# Schematic_Radio_EasyEDA.net
KiCad netlist of a schematic drawn in EasyEDA
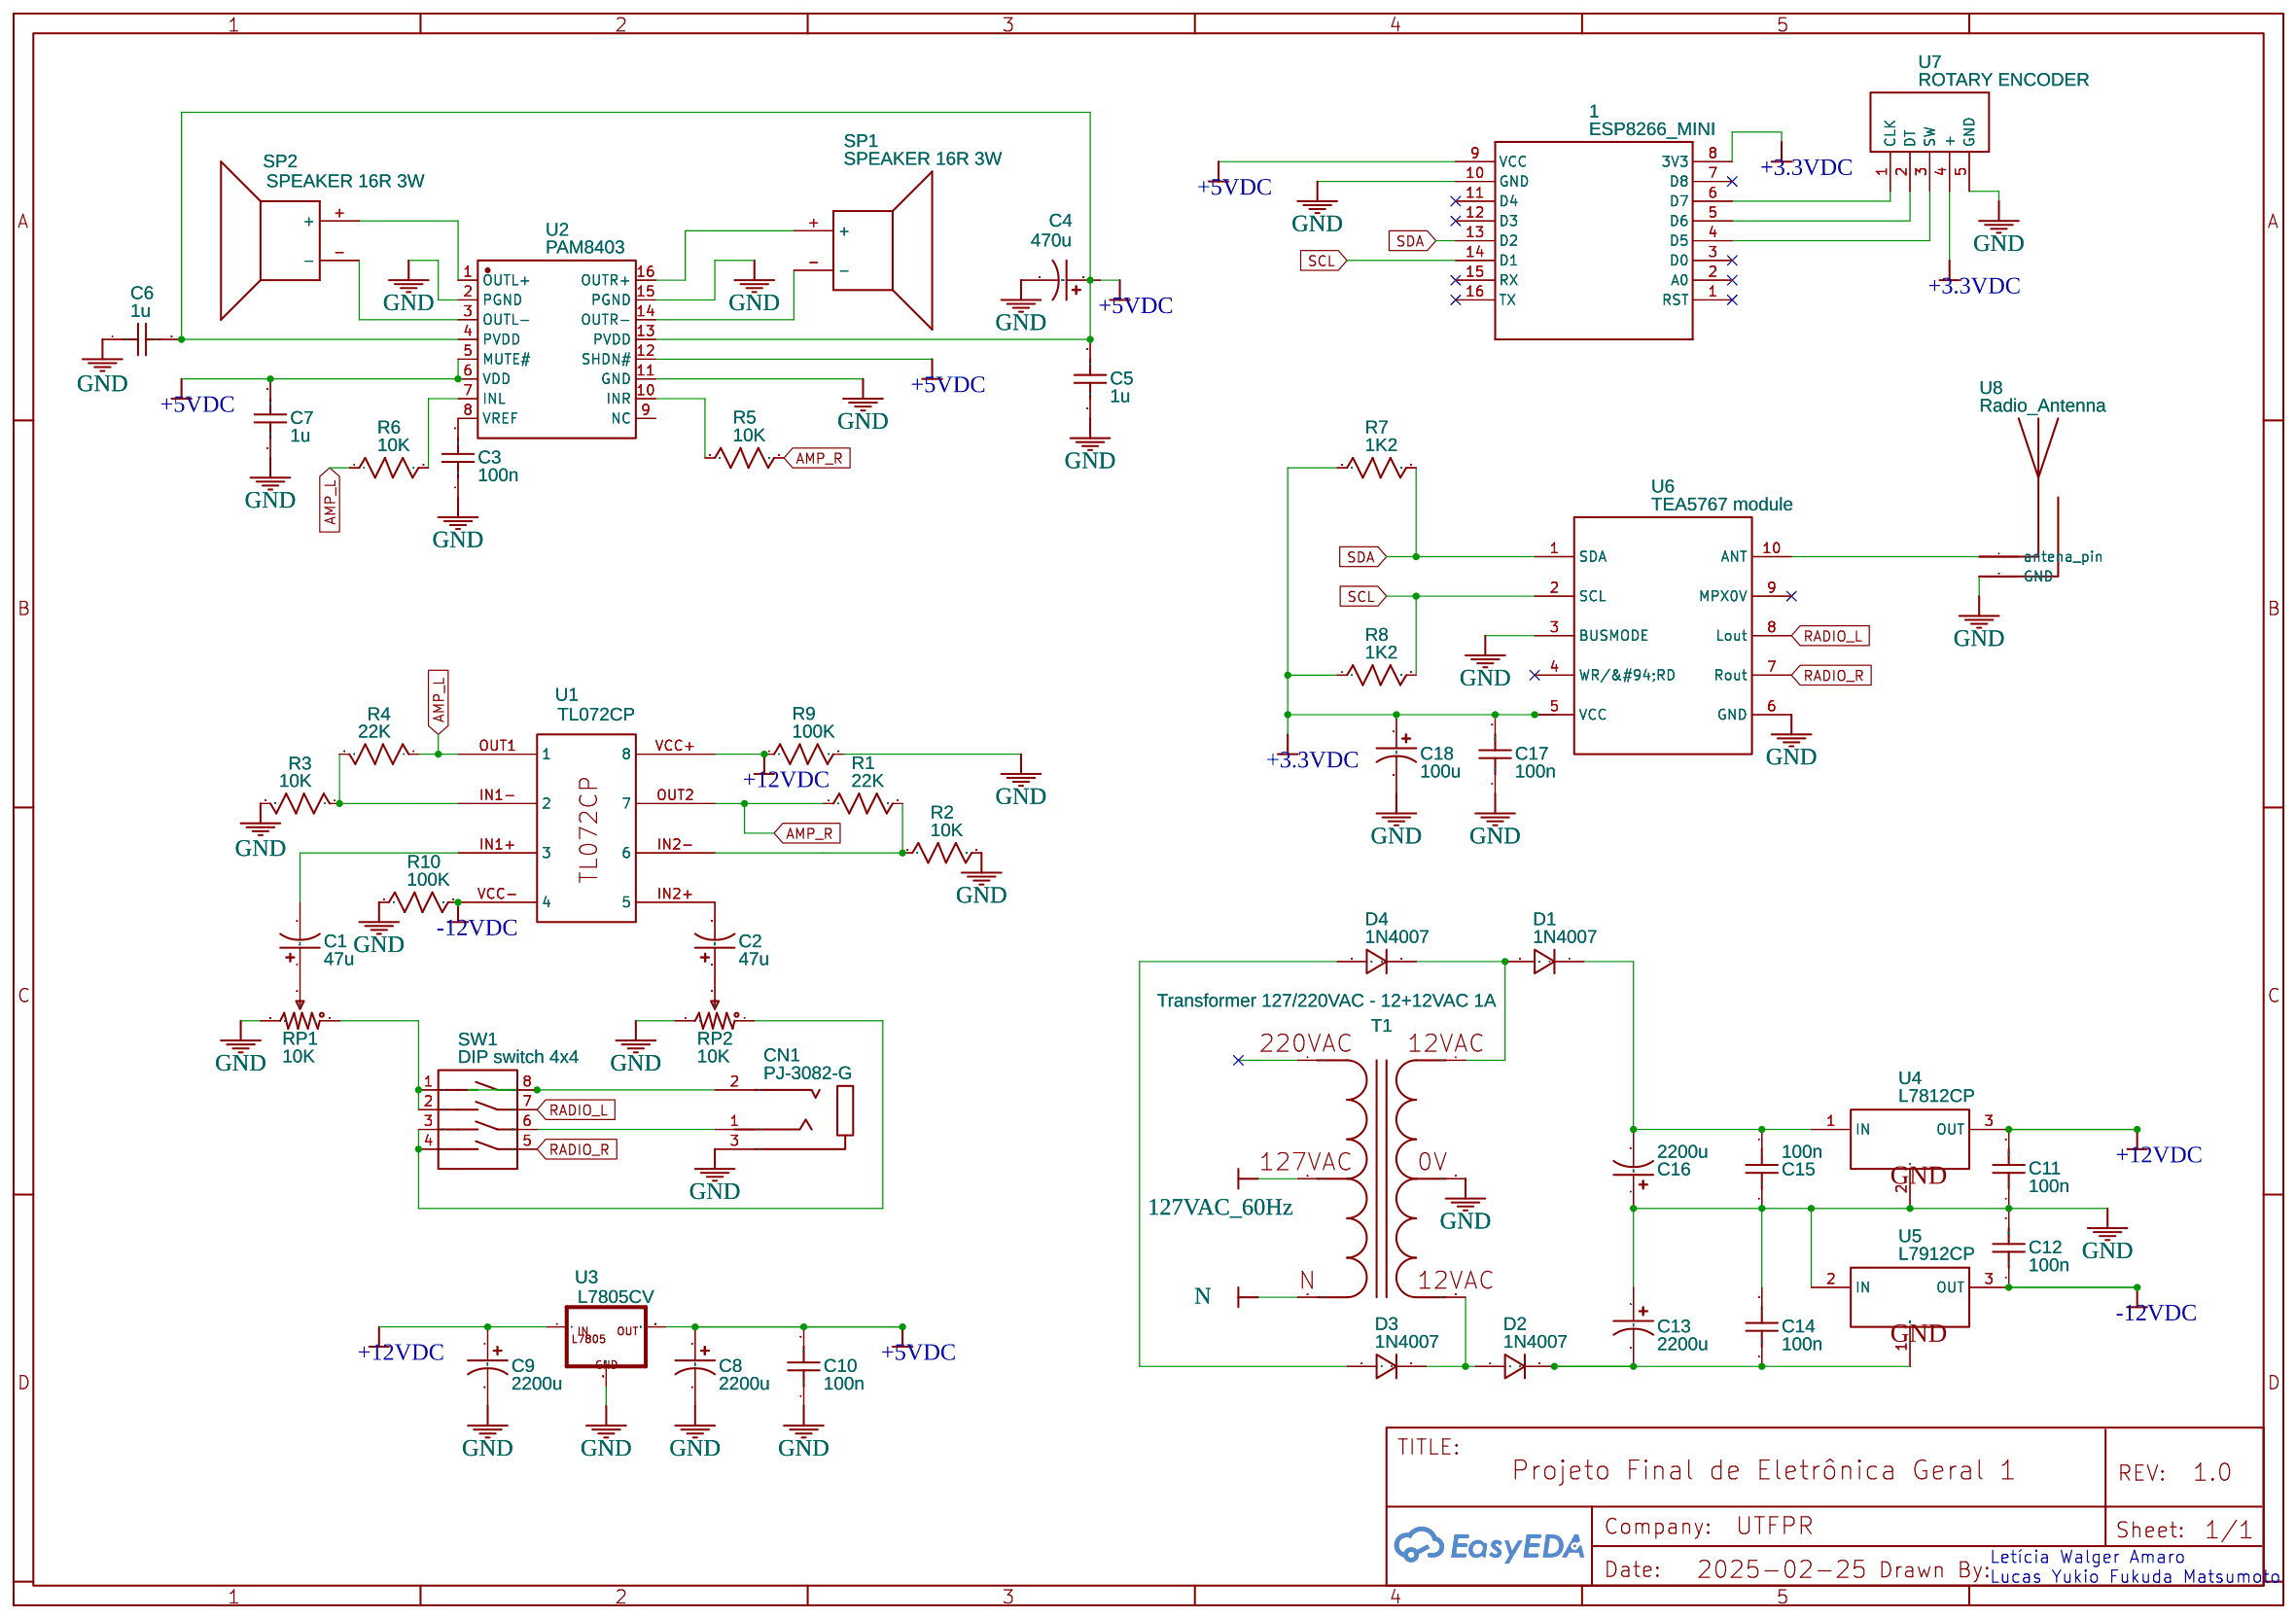
[diagram p0: schematic sheet]

(export (version "E")
  (design (tool "Eeschema 10.0.6"))
  (components
    (comp (ref "1") (value "ESP8266_MINI") (libsource (lib "") (part "ESP8266MINI COPY")))
    (comp (ref "C1") (value "47u") (libsource (lib "") (part "C_Tan_SMD_A_US_5")))
    (comp (ref "C2") (value "47u") (libsource (lib "") (part "C_Tan_SMD_A_US_2")))
    (comp (ref "C3") (value "100n") (libsource (lib "") (part "C_0603_US")))
    (comp (ref "C4") (value "470u") (libsource (lib "") (part "C_Tan_SMD_A_US_3")))
    (comp (ref "C5") (value "1u") (libsource (lib "") (part "C_0603_US")))
    (comp (ref "C6") (value "1u") (libsource (lib "") (part "C_0603_US_1")))
    (comp (ref "C7") (value "1u") (libsource (lib "") (part "C_0603_US")))
    (comp (ref "C8") (value "2200u") (libsource (lib "") (part "C_Tan_SMD_A_US_1")))
    (comp (ref "C9") (value "2200u") (libsource (lib "") (part "C_Tan_SMD_A_US_4")))
    (comp (ref "C10") (value "100n") (libsource (lib "") (part "C_0603_US")))
    (comp (ref "C11") (value "100n") (libsource (lib "") (part "C_0603_US")))
    (comp (ref "C12") (value "100n") (libsource (lib "") (part "C_0603_US")))
    (comp (ref "C13") (value "2200u") (libsource (lib "") (part "C_Tan_SMD_A_US_1")))
    (comp (ref "C14") (value "100n") (libsource (lib "") (part "C_0603_US")))
    (comp (ref "C15") (value "100n") (libsource (lib "") (part "C_0603_US_2")))
    (comp (ref "C16") (value "2200u") (libsource (lib "") (part "C_Tan_SMD_A_US")))
    (comp (ref "C17") (value "100n") (libsource (lib "") (part "C_0603_US")))
    (comp (ref "C18") (value "100u") (libsource (lib "") (part "C_Tan_SMD_A_US_6")))
    (comp (ref "CN1")
      (value "PJ-3082-G")
      (fields
        (field (name "Manufacturer Part") "PJ-3733")
        (field (name "Manufacturer") "XKB Connection(中国星坤)")
      )
      (libsource (lib "") (part "PJ-3733"))
    )
    (comp (ref "D1")
      (value "1N4007")
      (fields (field (name "Manufacturer Part") "1N4007W") (field (name "Manufacturer") "BLUE ROCKET"))
      (libsource (lib "") (part "1N4007W"))
    )
    (comp (ref "D2")
      (value "1N4007")
      (fields (field (name "Manufacturer Part") "1N4007W") (field (name "Manufacturer") "BLUE ROCKET"))
      (libsource (lib "") (part "1N4007W"))
    )
    (comp (ref "D3")
      (value "1N4007")
      (fields (field (name "Manufacturer Part") "1N4007W") (field (name "Manufacturer") "BLUE ROCKET"))
      (libsource (lib "") (part "1N4007W"))
    )
    (comp (ref "D4")
      (value "1N4007")
      (fields (field (name "Manufacturer Part") "1N4007W") (field (name "Manufacturer") "BLUE ROCKET"))
      (libsource (lib "") (part "1N4007W"))
    )
    (comp (ref "R1") (value "22K") (libsource (lib "") (part "R_0603_US_1")))
    (comp (ref "R2") (value "10K") (libsource (lib "") (part "R_0603_US_1")))
    (comp (ref "R3") (value "10K") (libsource (lib "") (part "R_0603_US")))
    (comp (ref "R4") (value "22K") (libsource (lib "") (part "R_0603_US")))
    (comp (ref "R5") (value "10K") (libsource (lib "") (part "R_0603_US_1")))
    (comp (ref "R6") (value "10K") (libsource (lib "") (part "R_0603_US_1")))
    (comp (ref "R7") (value "1K2") (libsource (lib "") (part "R_0603_US_1")))
    (comp (ref "R8") (value "1K2") (libsource (lib "") (part "R_0603_US_1")))
    (comp (ref "R9") (value "100K") (libsource (lib "") (part "R_0603_US_1")))
    (comp (ref "R10") (value "100K") (libsource (lib "") (part "R_0603_US_1")))
    (comp (ref "RP1") (value "10K") (libsource (lib "") (part "R_3386P_US")))
    (comp (ref "RP2") (value "10K") (libsource (lib "") (part "R_3386P_US")))
    (comp (ref "SP1") (value "SPEAKER 16R 3W") (libsource (lib "") (part "SPEAKER_1")))
    (comp (ref "SP2") (value "SPEAKER 16R 3W") (libsource (lib "") (part "SPEAKER")))
    (comp (ref "SW1")
      (value "DIP switch 4x4")
      (fields (field (name "Manufacturer Part") "拨码开关EI-04") (field (name "Manufacturer") "圜达"))
      (libsource (lib "") (part "DIP switchEI-04"))
    )
    (comp (ref "T1")
      (value "Transformer 127/220VAC - 12+12VAC 1A")
      (fields (field (name "Manufacturer Part") "TTG-6C33CPP") (field (name "Manufacturer") "Toroidy"))
      (libsource (lib "") (part "Transformer"))
    )
    (comp (ref "U1")
      (value "TL072CP")
      (fields (field (name "Manufacturer") "TI(德州仪器)"))
      (libsource (lib "") (part "TL072CP"))
    )
    (comp (ref "U2")
      (value "PAM8403")
      (fields (field (name "Manufacturer") "Slkor(萨科微)"))
      (libsource (lib "") (part "PAM8403"))
    )
    (comp (ref "U3") (value "L7805CV") (libsource (lib "") (part "-L7805")))
    (comp (ref "U4") (value "L7812CP") (libsource (lib "") (part "L7812CP")))
    (comp (ref "U5") (value "L7912CP") (libsource (lib "") (part "L7912CP")))
    (comp (ref "U6")
      (value "TEA5767 module")
      (fields (field (name "Manufacturer Part") "TEA5767"))
      (libsource (lib "") (part "TEA5767 module"))
    )
    (comp (ref "U7") (value "ROTARY ENCODER") (libsource (lib "") (part "ROTARY ENCODER (BREAKOUT)")))
    (comp (ref "U8") (value "Radio_Antenna") (libsource (lib "") (part "Radio_Antenna")))
  )
  (nets
    (net (code "1") (name "+3.3VDC") (class "Default")
      (node (ref "1") (pin "8") (pinfunction "3V3_8") (pintype "bidirectional"))
      (node (ref "C17") (pin "2") (pinfunction "2_2") (pintype "unspecified"))
      (node (ref "C18") (pin "1") (pinfunction "1_1") (pintype "unspecified"))
      (node (ref "R7") (pin "1") (pinfunction "1_1") (pintype "unspecified"))
      (node (ref "R8") (pin "1") (pinfunction "1_1") (pintype "unspecified"))
      (node (ref "U6") (pin "5") (pinfunction "VCC_5") (pintype "unspecified"))
      (node (ref "U7") (pin "4") (pinfunction "+_4") (pintype "unspecified"))
    )
    (net (code "2") (name "+5VDC") (class "Default")
      (node (ref "1") (pin "9") (pinfunction "VCC_9") (pintype "bidirectional"))
      (node (ref "C10") (pin "2") (pinfunction "2_2") (pintype "unspecified"))
      (node (ref "C4") (pin "1") (pinfunction "1_1") (pintype "unspecified"))
      (node (ref "C7") (pin "2") (pinfunction "2_2") (pintype "unspecified"))
      (node (ref "C8") (pin "1") (pinfunction "1_1") (pintype "unspecified"))
      (node (ref "U2") (pin "12") (pinfunction "SHDN#_12") (pintype "unspecified"))
      (node (ref "U2") (pin "5") (pinfunction "MUTE#_5") (pintype "unspecified"))
      (node (ref "U2") (pin "6") (pinfunction "VDD_6") (pintype "unspecified"))
      (node (ref "U3") (pin "OUT") (pinfunction "OUT_OUT") (pintype "unspecified"))
    )
    (net (code "3") (name "+12VDC") (class "Default")
      (node (ref "C11") (pin "2") (pinfunction "2_2") (pintype "unspecified"))
      (node (ref "C9") (pin "1") (pinfunction "1_1") (pintype "unspecified"))
      (node (ref "R9") (pin "1") (pinfunction "1_1") (pintype "unspecified"))
      (node (ref "U1") (pin "VCC+") (pinfunction "8_VCC+") (pintype "unspecified"))
      (node (ref "U3") (pin "IN") (pinfunction "IN_IN") (pintype "input"))
      (node (ref "U4") (pin "3") (pinfunction "OUT_3") (pintype "passive"))
    )
    (net (code "4") (name "-12VDC") (class "Default")
      (node (ref "C12") (pin "1") (pinfunction "1_1") (pintype "unspecified"))
      (node (ref "R10") (pin "2") (pinfunction "2_2") (pintype "unspecified"))
      (node (ref "U1") (pin "VCC-") (pinfunction "4_VCC-") (pintype "unspecified"))
      (node (ref "U5") (pin "3") (pinfunction "OUT_3") (pintype "passive"))
    )
    (net (code "5") (name "127VAC_60Hz") (class "Default")
      (node (ref "T1") (pin "2") (pinfunction "2_2") (pintype "unspecified"))
    )
    (net (code "6") (name "AMP_L") (class "Default")
      (node (ref "R4") (pin "1") (pinfunction "1_1") (pintype "unspecified"))
      (node (ref "R6") (pin "1") (pinfunction "1_1") (pintype "unspecified"))
      (node (ref "U1") (pin "OUT1") (pinfunction "1_OUT1") (pintype "unspecified"))
    )
    (net (code "7") (name "AMP_R") (class "Default")
      (node (ref "R1") (pin "1") (pinfunction "1_1") (pintype "unspecified"))
      (node (ref "R5") (pin "2") (pinfunction "2_2") (pintype "unspecified"))
      (node (ref "U1") (pin "OUT2") (pinfunction "7_OUT2") (pintype "unspecified"))
    )
    (net (code "8") (name "GND") (class "Default")
      (node (ref "1") (pin "10") (pinfunction "GND_10") (pintype "bidirectional"))
      (node (ref "C10") (pin "1") (pinfunction "1_1") (pintype "unspecified"))
      (node (ref "C11") (pin "1") (pinfunction "1_1") (pintype "unspecified"))
      (node (ref "C12") (pin "2") (pinfunction "2_2") (pintype "unspecified"))
      (node (ref "C13") (pin "1") (pinfunction "1_1") (pintype "unspecified"))
      (node (ref "C14") (pin "2") (pinfunction "2_2") (pintype "unspecified"))
      (node (ref "C15") (pin "2") (pinfunction "2_2") (pintype "unspecified"))
      (node (ref "C16") (pin "1") (pinfunction "1_1") (pintype "unspecified"))
      (node (ref "C17") (pin "1") (pinfunction "1_1") (pintype "unspecified"))
      (node (ref "C18") (pin "2") (pinfunction "2_2") (pintype "unspecified"))
      (node (ref "C3") (pin "1") (pinfunction "1_1") (pintype "unspecified"))
      (node (ref "C4") (pin "2") (pinfunction "2_2") (pintype "unspecified"))
      (node (ref "C5") (pin "1") (pinfunction "1_1") (pintype "unspecified"))
      (node (ref "C6") (pin "1") (pinfunction "1_1") (pintype "unspecified"))
      (node (ref "C7") (pin "1") (pinfunction "1_1") (pintype "unspecified"))
      (node (ref "C8") (pin "2") (pinfunction "2_2") (pintype "unspecified"))
      (node (ref "C9") (pin "2") (pinfunction "2_2") (pintype "unspecified"))
      (node (ref "CN1") (pin "3") (pinfunction "3_3") (pintype "unspecified"))
      (node (ref "R10") (pin "1") (pinfunction "1_1") (pintype "unspecified"))
      (node (ref "R2") (pin "2") (pinfunction "2_2") (pintype "unspecified"))
      (node (ref "R3") (pin "2") (pinfunction "2_2") (pintype "unspecified"))
      (node (ref "R9") (pin "2") (pinfunction "2_2") (pintype "unspecified"))
      (node (ref "RP1") (pin "3") (pinfunction "3_3") (pintype "unspecified"))
      (node (ref "RP2") (pin "3") (pinfunction "3_3") (pintype "unspecified"))
      (node (ref "T1") (pin "5") (pinfunction "5_5") (pintype "unspecified"))
      (node (ref "U2") (pin "11") (pinfunction "GND_11") (pintype "unspecified"))
      (node (ref "U2") (pin "15") (pinfunction "PGND_15") (pintype "unspecified"))
      (node (ref "U2") (pin "2") (pinfunction "PGND_2") (pintype "unspecified"))
      (node (ref "U3") (pin "GND") (pinfunction "GND_GND") (pintype "input"))
      (node (ref "U4") (pin "2") (pinfunction "GND_2") (pintype "passive"))
      (node (ref "U5") (pin "2") (pinfunction "IN_2") (pintype "passive"))
      (node (ref "U6") (pin "3") (pinfunction "BUSMODE_3") (pintype "unspecified"))
      (node (ref "U6") (pin "6") (pinfunction "GND_6") (pintype "unspecified"))
      (node (ref "U7") (pin "5") (pinfunction "GND_5") (pintype "unspecified"))
      (node (ref "U8") (pin "2") (pinfunction "GND_2") (pintype "unspecified"))
    )
    (net (code "9") (name "N") (class "Default")
      (node (ref "T1") (pin "3") (pinfunction "3_3") (pintype "unspecified"))
    )
    (net (code "10") (name "Net-(1-D5)") (class "Default")
      (node (ref "1") (pin "4") (pinfunction "D5_4") (pintype "bidirectional"))
      (node (ref "U7") (pin "3") (pinfunction "SW_3") (pintype "unspecified"))
    )
    (net (code "11") (name "Net-(1-D6)") (class "Default")
      (node (ref "1") (pin "5") (pinfunction "D6_5") (pintype "bidirectional"))
      (node (ref "U7") (pin "2") (pinfunction "DT_2") (pintype "unspecified"))
    )
    (net (code "12") (name "Net-(1-D7)") (class "Default")
      (node (ref "1") (pin "6") (pinfunction "D7_6") (pintype "bidirectional"))
      (node (ref "U7") (pin "1") (pinfunction "CLK_1") (pintype "unspecified"))
    )
    (net (code "13") (name "Net-(C1-Pad1)") (class "Default")
      (node (ref "C1") (pin "1") (pinfunction "1_1") (pintype "unspecified"))
      (node (ref "RP1") (pin "2") (pinfunction "2_2") (pintype "unspecified"))
    )
    (net (code "14") (name "Net-(C2-Pad1)") (class "Default")
      (node (ref "C2") (pin "1") (pinfunction "1_1") (pintype "unspecified"))
      (node (ref "RP2") (pin "2") (pinfunction "2_2") (pintype "unspecified"))
    )
    (net (code "15") (name "Net-(C5-Pad2)") (class "Default")
      (node (ref "C5") (pin "2") (pinfunction "2_2") (pintype "unspecified"))
      (node (ref "C6") (pin "2") (pinfunction "2_2") (pintype "unspecified"))
      (node (ref "U2") (pin "13") (pinfunction "PVDD_13") (pintype "unspecified"))
      (node (ref "U2") (pin "4") (pinfunction "PVDD_4") (pintype "unspecified"))
    )
    (net (code "16") (name "Net-(CN1-Pad1)") (class "Default")
      (node (ref "CN1") (pin "1") (pinfunction "1_1") (pintype "unspecified"))
      (node (ref "SW1") (pin "6") (pinfunction "6_6") (pintype "unspecified"))
    )
    (net (code "17") (name "Net-(CN1-Pad2)") (class "Default")
      (node (ref "CN1") (pin "2") (pinfunction "2_2") (pintype "unspecified"))
      (node (ref "SW1") (pin "8") (pinfunction "8_8") (pintype "unspecified"))
    )
    (net (code "18") (name "Net-(D1-Pad2)") (class "Default")
      (node (ref "D1") (pin "2") (pinfunction "2_2") (pintype "unspecified"))
      (node (ref "D4") (pin "1") (pinfunction "1_1") (pintype "unspecified"))
      (node (ref "T1") (pin "4") (pinfunction "4_4") (pintype "unspecified"))
    )
    (net (code "19") (name "Net-(D2-Pad2)") (class "Default")
      (node (ref "D2") (pin "2") (pinfunction "2_2") (pintype "unspecified"))
      (node (ref "D3") (pin "1") (pinfunction "1_1") (pintype "unspecified"))
      (node (ref "T1") (pin "6") (pinfunction "6_6") (pintype "unspecified"))
    )
    (net (code "20") (name "Net-(D3-Pad2)") (class "Default")
      (node (ref "D3") (pin "2") (pinfunction "2_2") (pintype "unspecified"))
      (node (ref "D4") (pin "2") (pinfunction "2_2") (pintype "unspecified"))
    )
    (net (code "21") (name "Net-(RP1-Pad1)") (class "Default")
      (node (ref "RP1") (pin "1") (pinfunction "1_1") (pintype "unspecified"))
      (node (ref "SW1") (pin "1") (pinfunction "1_1") (pintype "unspecified"))
      (node (ref "SW1") (pin "2") (pinfunction "2_2") (pintype "unspecified"))
    )
    (net (code "22") (name "Net-(RP2-Pad1)") (class "Default")
      (node (ref "RP2") (pin "1") (pinfunction "1_1") (pintype "unspecified"))
      (node (ref "SW1") (pin "3") (pinfunction "3_3") (pintype "unspecified"))
      (node (ref "SW1") (pin "4") (pinfunction "4_4") (pintype "unspecified"))
    )
    (net (code "23") (name "Net-(U1-2)") (class "Default")
      (node (ref "R3") (pin "1") (pinfunction "1_1") (pintype "unspecified"))
      (node (ref "R4") (pin "2") (pinfunction "2_2") (pintype "unspecified"))
      (node (ref "U1") (pin "IN1-") (pinfunction "2_IN1-") (pintype "unspecified"))
    )
    (net (code "24") (name "Net-(U1-3)") (class "Default")
      (node (ref "C1") (pin "2") (pinfunction "2_2") (pintype "unspecified"))
      (node (ref "U1") (pin "IN1+") (pinfunction "3_IN1+") (pintype "unspecified"))
    )
    (net (code "25") (name "Net-(U1-5)") (class "Default")
      (node (ref "C2") (pin "2") (pinfunction "2_2") (pintype "unspecified"))
      (node (ref "U1") (pin "IN2+") (pinfunction "5_IN2+") (pintype "unspecified"))
    )
    (net (code "26") (name "Net-(U1-6)") (class "Default")
      (node (ref "R1") (pin "2") (pinfunction "2_2") (pintype "unspecified"))
      (node (ref "R2") (pin "1") (pinfunction "1_1") (pintype "unspecified"))
      (node (ref "U1") (pin "IN2-") (pinfunction "6_IN2-") (pintype "unspecified"))
    )
    (net (code "27") (name "Net-(U2-INL)") (class "Default")
      (node (ref "R6") (pin "2") (pinfunction "2_2") (pintype "unspecified"))
      (node (ref "U2") (pin "7") (pinfunction "INL_7") (pintype "unspecified"))
    )
    (net (code "28") (name "Net-(U2-INR)") (class "Default")
      (node (ref "R5") (pin "1") (pinfunction "1_1") (pintype "unspecified"))
      (node (ref "U2") (pin "10") (pinfunction "INR_10") (pintype "unspecified"))
    )
    (net (code "29") (name "Net-(U2-OUTL+)") (class "Default")
      (node (ref "SP2") (pin "+") (pinfunction "+_+") (pintype "unspecified"))
      (node (ref "U2") (pin "1") (pinfunction "OUTL+_1") (pintype "unspecified"))
    )
    (net (code "30") (name "Net-(U2-OUTL-)") (class "Default")
      (node (ref "SP2") (pin "-") (pinfunction "-_-") (pintype "unspecified"))
      (node (ref "U2") (pin "3") (pinfunction "OUTL-_3") (pintype "unspecified"))
    )
    (net (code "31") (name "Net-(U2-OUTR+)") (class "Default")
      (node (ref "SP1") (pin "+") (pinfunction "+_+") (pintype "unspecified"))
      (node (ref "U2") (pin "16") (pinfunction "OUTR+_16") (pintype "unspecified"))
    )
    (net (code "32") (name "Net-(U2-OUTR-)") (class "Default")
      (node (ref "SP1") (pin "-") (pinfunction "-_-") (pintype "unspecified"))
      (node (ref "U2") (pin "14") (pinfunction "OUTR-_14") (pintype "unspecified"))
    )
    (net (code "33") (name "Net-(U2-VREF)") (class "Default")
      (node (ref "C3") (pin "2") (pinfunction "2_2") (pintype "unspecified"))
      (node (ref "U2") (pin "8") (pinfunction "VREF_8") (pintype "unspecified"))
    )
    (net (code "34") (name "Net-(U4-IN)") (class "Default")
      (node (ref "C15") (pin "1") (pinfunction "1_1") (pintype "unspecified"))
      (node (ref "C16") (pin "2") (pinfunction "2_2") (pintype "unspecified"))
      (node (ref "D1") (pin "1") (pinfunction "1_1") (pintype "unspecified"))
      (node (ref "U4") (pin "1") (pinfunction "IN_1") (pintype "passive"))
    )
    (net (code "35") (name "Net-(U5-GND)") (class "Default")
      (node (ref "C13") (pin "2") (pinfunction "2_2") (pintype "unspecified"))
      (node (ref "C14") (pin "1") (pinfunction "1_1") (pintype "unspecified"))
      (node (ref "D2") (pin "1") (pinfunction "1_1") (pintype "unspecified"))
      (node (ref "U5") (pin "1") (pinfunction "GND_1") (pintype "passive"))
    )
    (net (code "36") (name "Net-(U6-ANT)") (class "Default")
      (node (ref "U6") (pin "10") (pinfunction "ANT_10") (pintype "unspecified"))
      (node (ref "U8") (pin "1") (pinfunction "antena_pin_1") (pintype "unspecified"))
    )
    (net (code "37") (name "RADIO_L") (class "Default")
      (node (ref "SW1") (pin "7") (pinfunction "7_7") (pintype "unspecified"))
      (node (ref "U6") (pin "8") (pinfunction "Lout_8") (pintype "unspecified"))
    )
    (net (code "38") (name "RADIO_R") (class "Default")
      (node (ref "SW1") (pin "5") (pinfunction "5_5") (pintype "unspecified"))
      (node (ref "U6") (pin "7") (pinfunction "Rout_7") (pintype "unspecified"))
    )
    (net (code "39") (name "SCL") (class "Default")
      (node (ref "1") (pin "14") (pinfunction "D1_14") (pintype "bidirectional"))
      (node (ref "R8") (pin "2") (pinfunction "2_2") (pintype "unspecified"))
      (node (ref "U6") (pin "2") (pinfunction "SCL_2") (pintype "unspecified"))
    )
    (net (code "40") (name "SDA") (class "Default")
      (node (ref "1") (pin "13") (pinfunction "D2_13") (pintype "bidirectional"))
      (node (ref "R7") (pin "2") (pinfunction "2_2") (pintype "unspecified"))
      (node (ref "U6") (pin "1") (pinfunction "SDA_1") (pintype "unspecified"))
    )
    (net (code "41") (name "unconnected-(1-A0-Pad2)") (class "Default")
      (node (ref "1") (pin "2") (pinfunction "A0_2") (pintype "bidirectional+no_connect"))
    )
    (net (code "42") (name "unconnected-(1-D0-Pad3)") (class "Default")
      (node (ref "1") (pin "3") (pinfunction "D0_3") (pintype "bidirectional+no_connect"))
    )
    (net (code "43") (name "unconnected-(1-D3-Pad12)") (class "Default")
      (node (ref "1") (pin "12") (pinfunction "D3_12") (pintype "bidirectional+no_connect"))
    )
    (net (code "44") (name "unconnected-(1-D4-Pad11)") (class "Default")
      (node (ref "1") (pin "11") (pinfunction "D4_11") (pintype "bidirectional+no_connect"))
    )
    (net (code "45") (name "unconnected-(1-D8-Pad7)") (class "Default")
      (node (ref "1") (pin "7") (pinfunction "D8_7") (pintype "bidirectional+no_connect"))
    )
    (net (code "46") (name "unconnected-(1-RST-Pad1)") (class "Default")
      (node (ref "1") (pin "1") (pinfunction "RST_1") (pintype "bidirectional+no_connect"))
    )
    (net (code "47") (name "unconnected-(1-RX-Pad15)") (class "Default")
      (node (ref "1") (pin "15") (pinfunction "RX_15") (pintype "bidirectional+no_connect"))
    )
    (net (code "48") (name "unconnected-(1-TX-Pad16)") (class "Default")
      (node (ref "1") (pin "16") (pinfunction "TX_16") (pintype "bidirectional+no_connect"))
    )
    (net (code "49") (name "unconnected-(T1-Pad1)") (class "Default")
      (node (ref "T1") (pin "1") (pinfunction "1_1") (pintype "unspecified+no_connect"))
    )
    (net (code "50") (name "unconnected-(U2-NC-Pad9)") (class "Default")
      (node (ref "U2") (pin "9") (pinfunction "NC_9") (pintype "unspecified"))
    )
    (net (code "51") (name "unconnected-(U6-MPX0V-Pad9)") (class "Default")
      (node (ref "U6") (pin "9") (pinfunction "MPX0V_9") (pintype "unspecified+no_connect"))
    )
    (net (code "52") (name "unconnected-(U6-WR{slash}&#94;RD-Pad4)") (class "Default")
      (node (ref "U6") (pin "4") (pinfunction "WR/&#94;RD_4") (pintype "unspecified+no_connect"))
    )
  )
)
